# 3V3_rail.net
KiCad netlist of a schematic drawn in Altium Designer
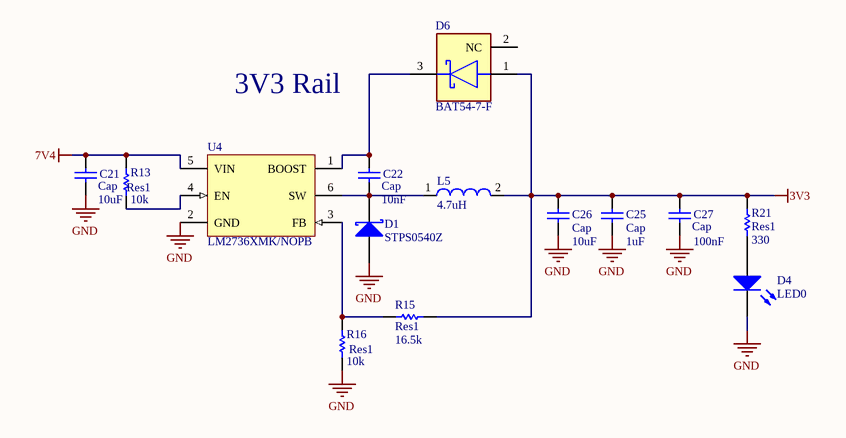
[diagram p0: 3V3 rail.SchDoc]

(export (version "E")
  (design (tool "Eeschema 10.0.6"))
  (components
    (comp (ref "C21")
      (value "Cap")
      (footprint "6-0805_M")
      (description "Capacitor")
      (fields (field (name "ALTIUM_VALUE") "10uF") (field (name "PUBLISHER") "Altium Limited"))
      (libsource (lib "Miscellaneous Devices") (part "Cap"))
    )
    (comp (ref "C22")
      (value "Cap")
      (footprint "0402-A")
      (description "Capacitor")
      (fields (field (name "ALTIUM_VALUE") "10nF") (field (name "PUBLISHER") "Altium Limited"))
      (libsource (lib "Miscellaneous Devices") (part "Cap"))
    )
    (comp (ref "C25")
      (value "Cap")
      (footprint "1608[0603]")
      (description "Capacitor")
      (fields (field (name "ALTIUM_VALUE") "1uF") (field (name "PUBLISHER") "Altium Limited"))
      (libsource (lib "Miscellaneous Devices") (part "Cap"))
    )
    (comp (ref "C26")
      (value "Cap")
      (footprint "6-0805_M")
      (description "Capacitor")
      (fields (field (name "ALTIUM_VALUE") "10uF") (field (name "PUBLISHER") "Altium Limited"))
      (libsource (lib "Miscellaneous Devices") (part "Cap"))
    )
    (comp (ref "C27")
      (value "Cap")
      (footprint "1608[0603]")
      (description "Capacitor")
      (fields (field (name "ALTIUM_VALUE") "100nF") (field (name "PUBLISHER") "Altium Limited"))
      (libsource (lib "Miscellaneous Devices") (part "Cap"))
    )
    (comp (ref "D1")
      (value "STPS0540Z")
      (footprint "STM-SOD-123-2_V")
      (description "Schottky Rectifier, 0.5 A, 40 V, 2-Pin SOP (SOD-123), RoHS, Tape and Reel")
      (fields (field (name "MANUFACTURER") "STMicroelectronics"))
      (libsource (lib "Altium Content Vault") (part "DSKY-AK-2"))
    )
    (comp (ref "D4")
      (value "LED0")
      (footprint "1608[0603]")
      (fields (field (name "PUBLISHER") "Altium Limited"))
      (libsource (lib "Miscellaneous Devices") (part "LED0"))
    )
    (comp (ref "D6")
      (value "BAT54-7-F")
      (footprint "FP-SOT23-MFG")
      (description "DIODE SCHOTTKY 30V 200MA SOT23-3")
      (fields
        (field (name "MANUFACTURER") "Diodes Inc.")
        (field (name "OCTOPART") "https://octopart.com/bat54-7-f-diodes+inc.-39681803")
      )
      (libsource (lib "Altium Content Vault") (part "c46c961685e925f3e7b53c7fd0df730"))
    )
    (comp (ref "L5")
      (value "4.7uH")
      (footprint "WE-TPC-4818-M")
      (description "SMD Shielded Tiny Power Inductor WE-TPC, L = 4.70 µH")
      (libsource (lib "Altium Content Vault") (part "PAS-IND-INDUCTOR-2"))
    )
    (comp (ref "R13")
      (value "Res1")
      (footprint "0402-A")
      (description "Resistor")
      (fields (field (name "ALTIUM_VALUE") "10k") (field (name "PUBLISHER") "Altium Limited"))
      (libsource (lib "Miscellaneous Devices") (part "Res1"))
    )
    (comp (ref "R15")
      (value "Res1")
      (footprint "0402-A")
      (description "Resistor")
      (fields (field (name "ALTIUM_VALUE") "16.5k") (field (name "PUBLISHER") "Altium Limited"))
      (libsource (lib "Miscellaneous Devices") (part "Res1"))
    )
    (comp (ref "R16")
      (value "Res1")
      (footprint "0402-A")
      (description "Resistor")
      (fields (field (name "ALTIUM_VALUE") "10k") (field (name "PUBLISHER") "Altium Limited"))
      (libsource (lib "Miscellaneous Devices") (part "Res1"))
    )
    (comp (ref "R21")
      (value "Res1")
      (footprint "0402-A")
      (description "Resistor")
      (fields (field (name "ALTIUM_VALUE") "330") (field (name "PUBLISHER") "Altium Limited"))
      (libsource (lib "Miscellaneous Devices") (part "Res1"))
    )
    (comp (ref "U4")
      (value "LM2736XMK/NOPB")
      (footprint "DDC0006A_L")
      (description "750mA Load Step-Down DC-DC Regulator, 6-pin Tiny SOT23, Pb-Free")
      (fields (field (name "MANUFACTURER") "Texas Instruments"))
      (libsource (lib "Altium Content Vault") (part "PM-DCDC-LM2736MK"))
    )
  )
  (nets
    (net (code "1") (name "3V3") (class "Default")
      (node (ref "C25") (pin "2") (pinfunction "2_2") (pintype "passive"))
      (node (ref "C26") (pin "2") (pinfunction "2_2") (pintype "passive"))
      (node (ref "C27") (pin "2") (pinfunction "2_2") (pintype "passive"))
      (node (ref "D6") (pin "1") (pinfunction "A_1") (pintype "passive"))
      (node (ref "L5") (pin "2") (pinfunction "2_2") (pintype "passive"))
      (node (ref "R15") (pin "1") (pinfunction "1_1") (pintype "passive"))
      (node (ref "R21") (pin "2") (pinfunction "2_2") (pintype "passive"))
    )
    (net (code "2") (name "7V4") (class "Default")
      (node (ref "C21") (pin "2") (pinfunction "2_2") (pintype "passive"))
      (node (ref "R13") (pin "2") (pinfunction "2_2") (pintype "passive"))
      (node (ref "U4") (pin "5") (pinfunction "VIN_5") (pintype "power_in"))
    )
    (net (code "3") (name "GND") (class "Default")
      (node (ref "C21") (pin "1") (pinfunction "1_1") (pintype "passive"))
      (node (ref "C25") (pin "1") (pinfunction "1_1") (pintype "passive"))
      (node (ref "C26") (pin "1") (pinfunction "1_1") (pintype "passive"))
      (node (ref "C27") (pin "1") (pinfunction "1_1") (pintype "passive"))
      (node (ref "D1") (pin "1") (pinfunction "A_1") (pintype "passive"))
      (node (ref "D4") (pin "2") (pinfunction "K_2") (pintype "passive"))
      (node (ref "R16") (pin "1") (pinfunction "1_1") (pintype "passive"))
      (node (ref "U4") (pin "2") (pinfunction "GND_2") (pintype "power_in"))
    )
    (net (code "4") (name "Net-(D1-K)") (class "Default")
      (node (ref "C22") (pin "1") (pinfunction "1_1") (pintype "passive"))
      (node (ref "D1") (pin "2") (pinfunction "K_2") (pintype "passive"))
      (node (ref "L5") (pin "1") (pinfunction "1_1") (pintype "passive"))
      (node (ref "U4") (pin "6") (pinfunction "SW_6") (pintype "power_in"))
    )
    (net (code "5") (name "Net-(D4-A)") (class "Default")
      (node (ref "D4") (pin "1") (pinfunction "A_1") (pintype "passive"))
      (node (ref "R21") (pin "1") (pinfunction "1_1") (pintype "passive"))
    )
    (net (code "6") (name "Net-(D6-C)") (class "Default")
      (node (ref "C22") (pin "2") (pinfunction "2_2") (pintype "passive"))
      (node (ref "D6") (pin "3") (pinfunction "C_3") (pintype "passive"))
      (node (ref "U4") (pin "1") (pinfunction "BOOST_1") (pintype "passive"))
    )
    (net (code "7") (name "Net-(U4-EN)") (class "Default")
      (node (ref "R13") (pin "1") (pinfunction "1_1") (pintype "passive"))
      (node (ref "U4") (pin "4") (pinfunction "EN_4") (pintype "input"))
    )
    (net (code "8") (name "Net-(U4-FB)") (class "Default")
      (node (ref "R15") (pin "2") (pinfunction "2_2") (pintype "passive"))
      (node (ref "R16") (pin "2") (pinfunction "2_2") (pintype "passive"))
      (node (ref "U4") (pin "3") (pinfunction "FB_3") (pintype "input"))
    )
    (net (code "9") (name "unconnected-(D6-NC-Pad2)") (class "Default")
      (node (ref "D6") (pin "2") (pinfunction "NC_2") (pintype "passive"))
    )
  )
)
